# charger.net
KiCad netlist of a schematic drawn in Altium Designer
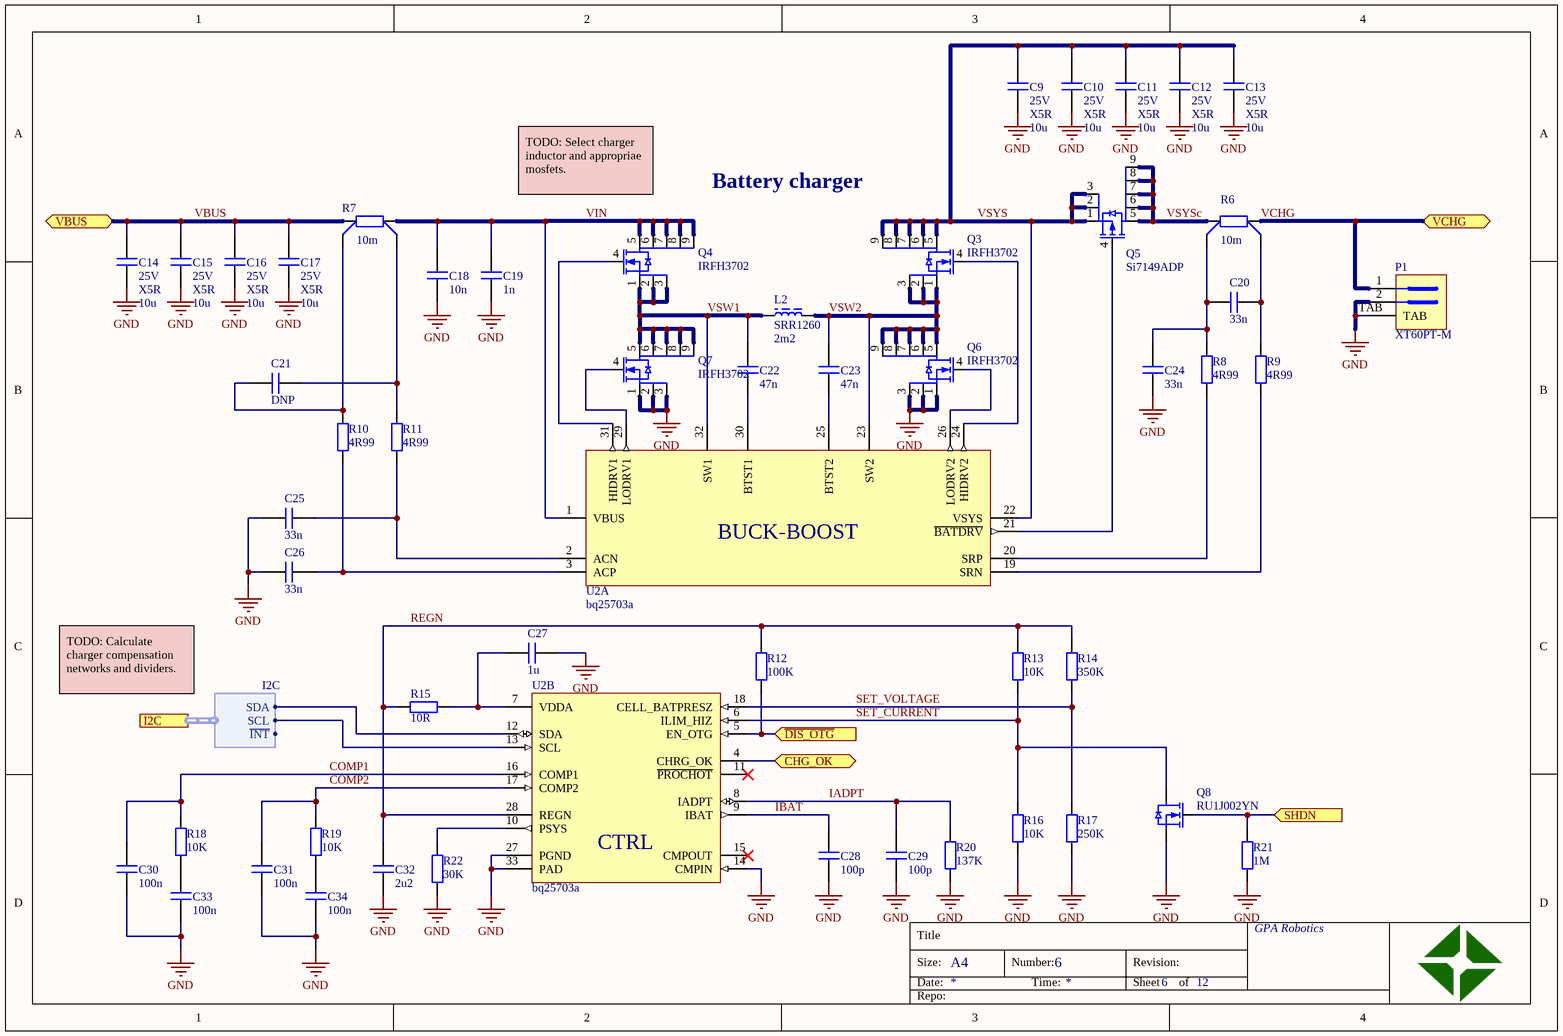
[diagram p0: charger.SchDoc]

(export (version "E")
  (design (tool "Eeschema 10.0.6"))
  (components
    (comp (ref "C9")
      (value "10u")
      (footprint "CAPC3216X14N")
      (description "Capacitor")
      (fields (field (name "VOLTAGE") "25V") (field (name "TYPE") "X5R") (field (name "Comment") "cap"))
      (libsource (lib "lib_passives") (part "cap"))
    )
    (comp (ref "C10")
      (value "10u")
      (footprint "CAPC3216X14N")
      (description "Capacitor")
      (fields (field (name "VOLTAGE") "25V") (field (name "TYPE") "X5R") (field (name "Comment") "cap"))
      (libsource (lib "lib_passives") (part "cap"))
    )
    (comp (ref "C11")
      (value "10u")
      (footprint "CAPC3216X14N")
      (description "Capacitor")
      (fields (field (name "VOLTAGE") "25V") (field (name "TYPE") "X5R") (field (name "Comment") "cap"))
      (libsource (lib "lib_passives") (part "cap"))
    )
    (comp (ref "C12")
      (value "10u")
      (footprint "CAPC3216X14N")
      (description "Capacitor")
      (fields (field (name "VOLTAGE") "25V") (field (name "TYPE") "X5R") (field (name "Comment") "cap"))
      (libsource (lib "lib_passives") (part "cap"))
    )
    (comp (ref "C13")
      (value "10u")
      (footprint "CAPC3216X14N")
      (description "Capacitor")
      (fields (field (name "VOLTAGE") "25V") (field (name "TYPE") "X5R") (field (name "Comment") "cap"))
      (libsource (lib "lib_passives") (part "cap"))
    )
    (comp (ref "C14")
      (value "10u")
      (footprint "CAPC3216X14N")
      (description "Capacitor")
      (fields (field (name "VOLTAGE") "25V") (field (name "TYPE") "X5R") (field (name "Comment") "cap"))
      (libsource (lib "lib_passives") (part "cap"))
    )
    (comp (ref "C15")
      (value "10u")
      (footprint "CAPC3216X14N")
      (description "Capacitor")
      (fields (field (name "VOLTAGE") "25V") (field (name "TYPE") "X5R") (field (name "Comment") "cap"))
      (libsource (lib "lib_passives") (part "cap"))
    )
    (comp (ref "C16")
      (value "10u")
      (footprint "CAPC3216X14N")
      (description "Capacitor")
      (fields (field (name "VOLTAGE") "25V") (field (name "TYPE") "X5R") (field (name "Comment") "cap"))
      (libsource (lib "lib_passives") (part "cap"))
    )
    (comp (ref "C17")
      (value "10u")
      (footprint "CAPC3216X14N")
      (description "Capacitor")
      (fields (field (name "VOLTAGE") "25V") (field (name "TYPE") "X5R") (field (name "Comment") "cap"))
      (libsource (lib "lib_passives") (part "cap"))
    )
    (comp (ref "C18")
      (value "10n")
      (footprint "CAPC1005X06N")
      (description "Capacitor")
      (fields (field (name "Comment") "cap"))
      (libsource (lib "lib_passives") (part "cap"))
    )
    (comp (ref "C19")
      (value "1n")
      (footprint "CAPC1005X06N")
      (description "Capacitor")
      (fields (field (name "Comment") "cap"))
      (libsource (lib "lib_passives") (part "cap"))
    )
    (comp (ref "C20")
      (value "33n")
      (footprint "CAPC1005X06N")
      (description "Capacitor")
      (fields (field (name "Comment") "cap"))
      (libsource (lib "lib_passives") (part "cap"))
    )
    (comp (ref "C21")
      (value "DNP")
      (footprint "CAPC1005X06N")
      (description "Capacitor")
      (fields (field (name "Comment") "cap"))
      (libsource (lib "lib_passives") (part "cap"))
    )
    (comp (ref "C22")
      (value "47n")
      (footprint "CAPC1005X06N")
      (description "Capacitor")
      (fields (field (name "Comment") "cap"))
      (libsource (lib "lib_passives") (part "cap"))
    )
    (comp (ref "C23")
      (value "47n")
      (footprint "CAPC1005X06N")
      (description "Capacitor")
      (fields (field (name "Comment") "cap"))
      (libsource (lib "lib_passives") (part "cap"))
    )
    (comp (ref "C24")
      (value "33n")
      (footprint "CAPC1005X06N")
      (description "Capacitor")
      (fields (field (name "Comment") "cap"))
      (libsource (lib "lib_passives") (part "cap"))
    )
    (comp (ref "C25")
      (value "33n")
      (footprint "CAPC1005X06N")
      (description "Capacitor")
      (fields (field (name "Comment") "cap"))
      (libsource (lib "lib_passives") (part "cap"))
    )
    (comp (ref "C26")
      (value "33n")
      (footprint "CAPC1005X06N")
      (description "Capacitor")
      (fields (field (name "Comment") "cap"))
      (libsource (lib "lib_passives") (part "cap"))
    )
    (comp (ref "C27")
      (value "1u")
      (footprint "CAPC2012X11N")
      (description "Capacitor")
      (fields (field (name "Comment") "cap"))
      (libsource (lib "lib_passives") (part "cap"))
    )
    (comp (ref "C28")
      (value "100p")
      (footprint "CAPC1005X06N")
      (description "Capacitor")
      (fields (field (name "Comment") "cap"))
      (libsource (lib "lib_passives") (part "cap"))
    )
    (comp (ref "C29")
      (value "100p")
      (footprint "CAPC1005X06N")
      (description "Capacitor")
      (fields (field (name "Comment") "cap"))
      (libsource (lib "lib_passives") (part "cap"))
    )
    (comp (ref "C30")
      (value "100n")
      (footprint "CAPC1005X06N")
      (description "Capacitor")
      (fields (field (name "Comment") "cap"))
      (libsource (lib "lib_passives") (part "cap"))
    )
    (comp (ref "C31")
      (value "100n")
      (footprint "CAPC1005X06N")
      (description "Capacitor")
      (fields (field (name "Comment") "cap"))
      (libsource (lib "lib_passives") (part "cap"))
    )
    (comp (ref "C32")
      (value "2u2")
      (footprint "CAPC2012X11N")
      (description "Capacitor")
      (fields (field (name "Comment") "cap"))
      (libsource (lib "lib_passives") (part "cap"))
    )
    (comp (ref "C33")
      (value "100n")
      (footprint "CAPC1005X06N")
      (description "Capacitor")
      (fields (field (name "Comment") "cap"))
      (libsource (lib "lib_passives") (part "cap"))
    )
    (comp (ref "C34")
      (value "100n")
      (footprint "CAPC1005X06N")
      (description "Capacitor")
      (fields (field (name "Comment") "cap"))
      (libsource (lib "lib_passives") (part "cap"))
    )
    (comp (ref "L2")
      (value "SRR1260")
      (footprint "SRR1260")
      (fields (field (name "ALTIUM_VALUE") "2m2"))
      (libsource (lib "lib_bourns") (part "srr1260"))
    )
    (comp (ref "P1")
      (value "XT60PT-M")
      (footprint "XT60PT-M")
      (libsource (lib "lib_amass") (part "xt60pt-m"))
    )
    (comp (ref "Q3")
      (value "IRFH3702")
      (footprint "PQFN67P300X300X100-8N")
      (description "HEXFET Power MOSFET")
      (libsource (lib "lib_infineon") (part "irfh3702"))
    )
    (comp (ref "Q4")
      (value "IRFH3702")
      (footprint "PQFN67P300X300X100-8N")
      (description "HEXFET Power MOSFET")
      (libsource (lib "lib_infineon") (part "irfh3702"))
    )
    (comp (ref "Q5")
      (value "Si7149ADP")
      (footprint "SON127P620X112_HS-9N_POWERPAK_SO8")
      (description "P-Channel 30 V (D-S) MOSFET")
      (libsource (lib "lib_vishay") (part "si7149adp"))
    )
    (comp (ref "Q6")
      (value "IRFH3702")
      (footprint "PQFN67P300X300X100-8N")
      (description "HEXFET Power MOSFET")
      (libsource (lib "lib_infineon") (part "irfh3702"))
    )
    (comp (ref "Q7")
      (value "IRFH3702")
      (footprint "PQFN67P300X300X100-8N")
      (description "HEXFET Power MOSFET")
      (libsource (lib "lib_infineon") (part "irfh3702"))
    )
    (comp (ref "Q8")
      (value "RU1J002YN")
      (footprint "SOTFL65P210X105-3N")
      (description "N-channel 50V 200mA Small signal MOSFET")
      (libsource (lib "lib_rohm") (part "ru1j002yn"))
    )
    (comp (ref "R6")
      (value "10m")
      (footprint "4T_RESC1632X05N")
      (description "Resistor")
      (fields (field (name "Comment") "res_4t"))
      (libsource (lib "") (part "res_4t_1"))
    )
    (comp (ref "R7")
      (value "10m")
      (footprint "4T_RESC1632X05N")
      (description "Resistor")
      (fields (field (name "Comment") "res_4t"))
      (libsource (lib "lib_passives") (part "res_4t"))
    )
    (comp (ref "R8")
      (value "4R99")
      (footprint "RESC1005X04N")
      (description "Resistor")
      (fields (field (name "Comment") "res"))
      (libsource (lib "lib_passives") (part "res"))
    )
    (comp (ref "R9")
      (value "4R99")
      (footprint "RESC1005X04N")
      (description "Resistor")
      (fields (field (name "Comment") "res"))
      (libsource (lib "lib_passives") (part "res"))
    )
    (comp (ref "R10")
      (value "4R99")
      (footprint "RESC1005X04N")
      (description "Resistor")
      (fields (field (name "Comment") "res"))
      (libsource (lib "lib_passives") (part "res"))
    )
    (comp (ref "R11")
      (value "4R99")
      (footprint "RESC1005X04N")
      (description "Resistor")
      (fields (field (name "Comment") "res"))
      (libsource (lib "lib_passives") (part "res"))
    )
    (comp (ref "R12")
      (value "100K")
      (footprint "RESC1005X04N")
      (description "Resistor")
      (fields (field (name "Comment") "res"))
      (libsource (lib "lib_passives") (part "res"))
    )
    (comp (ref "R13")
      (value "10K")
      (footprint "RESC1005X04N")
      (description "Resistor")
      (fields (field (name "Comment") "res"))
      (libsource (lib "lib_passives") (part "res"))
    )
    (comp (ref "R14")
      (value "350K")
      (footprint "RESC1005X04N")
      (description "Resistor")
      (fields (field (name "Comment") "res"))
      (libsource (lib "lib_passives") (part "res"))
    )
    (comp (ref "R15")
      (value "10R")
      (footprint "RESC1005X04N")
      (description "Resistor")
      (fields (field (name "Comment") "res"))
      (libsource (lib "") (part "res_1"))
    )
    (comp (ref "R16")
      (value "10K")
      (footprint "RESC1005X04N")
      (description "Resistor")
      (fields (field (name "Comment") "res"))
      (libsource (lib "lib_passives") (part "res"))
    )
    (comp (ref "R17")
      (value "250K")
      (footprint "RESC1005X04N")
      (description "Resistor")
      (fields (field (name "Comment") "res"))
      (libsource (lib "lib_passives") (part "res"))
    )
    (comp (ref "R18")
      (value "10K")
      (footprint "RESC1005X04N")
      (description "Resistor")
      (fields (field (name "Comment") "res"))
      (libsource (lib "lib_passives") (part "res"))
    )
    (comp (ref "R19")
      (value "10K")
      (footprint "RESC1005X04N")
      (description "Resistor")
      (fields (field (name "Comment") "res"))
      (libsource (lib "lib_passives") (part "res"))
    )
    (comp (ref "R20")
      (value "137K")
      (footprint "RESC1005X04N")
      (description "Resistor")
      (fields (field (name "Comment") "res"))
      (libsource (lib "lib_passives") (part "res"))
    )
    (comp (ref "R21")
      (value "1M")
      (footprint "RESC1005X04N")
      (description "Resistor")
      (fields (field (name "Comment") "res"))
      (libsource (lib "lib_passives") (part "res"))
    )
    (comp (ref "R22")
      (value "30K")
      (footprint "RESC1005X04N")
      (description "Resistor")
      (fields (field (name "Comment") "res"))
      (libsource (lib "lib_passives") (part "res"))
    )
    (comp (ref "U2")
      (value "bq25703a")
      (footprint "QFN40P400X400X80_HS-33N_BQ25703A")
      (libsource (lib "lib_ti") (part "bq25703a"))
    )
  )
  (nets
    (net (code "2") (name "/CHG_OK") (class "Default")
      (node (ref "U2") (pin "4") (pinfunction "CHRG_OK_4") (pintype "open_collector"))
    )
    (net (code "3") (name "/COMP1") (class "Default")
      (node (ref "C30") (pin "2") (pinfunction "2_2") (pintype "passive"))
      (node (ref "R18") (pin "2") (pinfunction "2_2") (pintype "passive"))
      (node (ref "U2") (pin "16") (pinfunction "COMP1_16") (pintype "input"))
    )
    (net (code "4") (name "/COMP2") (class "Default")
      (node (ref "C31") (pin "2") (pinfunction "2_2") (pintype "passive"))
      (node (ref "R19") (pin "2") (pinfunction "2_2") (pintype "passive"))
      (node (ref "U2") (pin "17") (pinfunction "COMP2_17") (pintype "input"))
    )
    (net (code "5") (name "/DIS_OTG") (class "Default")
      (node (ref "R12") (pin "1") (pinfunction "1_1") (pintype "passive"))
      (node (ref "U2") (pin "5") (pinfunction "EN_OTG_5") (pintype "input"))
    )
    (net (code "6") (name "/IADPT") (class "Default")
      (node (ref "C29") (pin "2") (pinfunction "2_2") (pintype "passive"))
      (node (ref "R20") (pin "2") (pinfunction "2_2") (pintype "passive"))
      (node (ref "U2") (pin "8") (pinfunction "IADPT_8") (pintype "bidirectional"))
    )
    (net (code "7") (name "/IBAT") (class "Default")
      (node (ref "C28") (pin "2") (pinfunction "2_2") (pintype "passive"))
      (node (ref "U2") (pin "9") (pinfunction "IBAT_9") (pintype "output"))
    )
    (net (code "8") (name "/REGN") (class "Default")
      (node (ref "C32") (pin "2") (pinfunction "2_2") (pintype "passive"))
      (node (ref "R12") (pin "2") (pinfunction "2_2") (pintype "passive"))
      (node (ref "R13") (pin "2") (pinfunction "2_2") (pintype "passive"))
      (node (ref "R14") (pin "2") (pinfunction "2_2") (pintype "passive"))
      (node (ref "R15") (pin "1") (pinfunction "1_1") (pintype "passive"))
      (node (ref "U2") (pin "28") (pinfunction "REGN_28") (pintype "power_in"))
    )
    (net (code "9") (name "/SCL") (class "Default")
      (node (ref "U2") (pin "13") (pinfunction "SCL_13") (pintype "input"))
    )
    (net (code "10") (name "/SDA") (class "Default")
      (node (ref "U2") (pin "12") (pinfunction "SDA_12") (pintype "bidirectional"))
    )
    (net (code "11") (name "/SET_CURRENT") (class "Default")
      (node (ref "Q8") (pin "3") (pinfunction "D_3") (pintype "passive"))
      (node (ref "R13") (pin "1") (pinfunction "1_1") (pintype "passive"))
      (node (ref "R16") (pin "2") (pinfunction "2_2") (pintype "passive"))
      (node (ref "U2") (pin "6") (pinfunction "ILIM_HIZ_6") (pintype "input"))
    )
    (net (code "12") (name "/SET_VOLTAGE") (class "Default")
      (node (ref "R14") (pin "1") (pinfunction "1_1") (pintype "passive"))
      (node (ref "R17") (pin "2") (pinfunction "2_2") (pintype "passive"))
      (node (ref "U2") (pin "18") (pinfunction "CELL_BATPRESZ_18") (pintype "input"))
    )
    (net (code "13") (name "/SHDN") (class "Default")
      (node (ref "Q8") (pin "1") (pinfunction "G_1") (pintype "passive"))
      (node (ref "R21") (pin "2") (pinfunction "2_2") (pintype "passive"))
    )
    (net (code "14") (name "/VBUS") (class "Default")
      (node (ref "C14") (pin "2") (pinfunction "2_2") (pintype "passive"))
      (node (ref "C15") (pin "2") (pinfunction "2_2") (pintype "passive"))
      (node (ref "C16") (pin "2") (pinfunction "2_2") (pintype "passive"))
      (node (ref "C17") (pin "2") (pinfunction "2_2") (pintype "passive"))
      (node (ref "R7") (pin "1") (pinfunction "1_1") (pintype "passive"))
    )
    (net (code "15") (name "/VCHG") (class "Default")
      (node (ref "P1") (pin "1") (pinfunction "1_1") (pintype "passive"))
      (node (ref "R6") (pin "1") (pinfunction "1_1") (pintype "passive"))
    )
    (net (code "16") (name "/VIN") (class "Default")
      (node (ref "C18") (pin "2") (pinfunction "2_2") (pintype "passive"))
      (node (ref "C19") (pin "2") (pinfunction "2_2") (pintype "passive"))
      (node (ref "Q4") (pin "5") (pinfunction "D_5") (pintype "passive"))
      (node (ref "Q4") (pin "6") (pinfunction "D_6") (pintype "passive"))
      (node (ref "Q4") (pin "7") (pinfunction "D_7") (pintype "passive"))
      (node (ref "Q4") (pin "8") (pinfunction "D_8") (pintype "passive"))
      (node (ref "Q4") (pin "9") (pinfunction "D_9") (pintype "passive"))
      (node (ref "R7") (pin "2") (pinfunction "2_2") (pintype "passive"))
      (node (ref "U2") (pin "1") (pinfunction "VBUS_1") (pintype "power_in"))
    )
    (net (code "17") (name "/VSW1") (class "Default")
      (node (ref "C22") (pin "2") (pinfunction "2_2") (pintype "passive"))
      (node (ref "L2") (pin "1") (pinfunction "1_1") (pintype "passive"))
      (node (ref "Q4") (pin "1") (pinfunction "S_1") (pintype "passive"))
      (node (ref "Q4") (pin "2") (pinfunction "S_2") (pintype "passive"))
      (node (ref "Q4") (pin "3") (pinfunction "S_3") (pintype "passive"))
      (node (ref "Q7") (pin "5") (pinfunction "D_5") (pintype "passive"))
      (node (ref "Q7") (pin "6") (pinfunction "D_6") (pintype "passive"))
      (node (ref "Q7") (pin "7") (pinfunction "D_7") (pintype "passive"))
      (node (ref "Q7") (pin "8") (pinfunction "D_8") (pintype "passive"))
      (node (ref "Q7") (pin "9") (pinfunction "D_9") (pintype "passive"))
      (node (ref "U2") (pin "32") (pinfunction "SW1_32") (pintype "power_in"))
    )
    (net (code "18") (name "/VSW2") (class "Default")
      (node (ref "C23") (pin "2") (pinfunction "2_2") (pintype "passive"))
      (node (ref "L2") (pin "2") (pinfunction "2_2") (pintype "passive"))
      (node (ref "Q3") (pin "1") (pinfunction "S_1") (pintype "passive"))
      (node (ref "Q3") (pin "2") (pinfunction "S_2") (pintype "passive"))
      (node (ref "Q3") (pin "3") (pinfunction "S_3") (pintype "passive"))
      (node (ref "Q6") (pin "5") (pinfunction "D_5") (pintype "passive"))
      (node (ref "Q6") (pin "6") (pinfunction "D_6") (pintype "passive"))
      (node (ref "Q6") (pin "7") (pinfunction "D_7") (pintype "passive"))
      (node (ref "Q6") (pin "8") (pinfunction "D_8") (pintype "passive"))
      (node (ref "Q6") (pin "9") (pinfunction "D_9") (pintype "passive"))
      (node (ref "U2") (pin "23") (pinfunction "SW2_23") (pintype "power_in"))
    )
    (net (code "19") (name "/VSYS") (class "Default")
      (node (ref "C10") (pin "2") (pinfunction "2_2") (pintype "passive"))
      (node (ref "C11") (pin "2") (pinfunction "2_2") (pintype "passive"))
      (node (ref "C12") (pin "2") (pinfunction "2_2") (pintype "passive"))
      (node (ref "C13") (pin "2") (pinfunction "2_2") (pintype "passive"))
      (node (ref "C9") (pin "2") (pinfunction "2_2") (pintype "passive"))
      (node (ref "Q3") (pin "5") (pinfunction "D_5") (pintype "passive"))
      (node (ref "Q3") (pin "6") (pinfunction "D_6") (pintype "passive"))
      (node (ref "Q3") (pin "7") (pinfunction "D_7") (pintype "passive"))
      (node (ref "Q3") (pin "8") (pinfunction "D_8") (pintype "passive"))
      (node (ref "Q3") (pin "9") (pinfunction "D_9") (pintype "passive"))
      (node (ref "Q5") (pin "1") (pinfunction "S_1") (pintype "passive"))
      (node (ref "Q5") (pin "2") (pinfunction "S_2") (pintype "passive"))
      (node (ref "Q5") (pin "3") (pinfunction "S_3") (pintype "passive"))
      (node (ref "U2") (pin "22") (pinfunction "VSYS_22") (pintype "power_in"))
    )
    (net (code "20") (name "/VSYSc") (class "Default")
      (node (ref "Q5") (pin "5") (pinfunction "D_5") (pintype "passive"))
      (node (ref "Q5") (pin "6") (pinfunction "D_6") (pintype "passive"))
      (node (ref "Q5") (pin "7") (pinfunction "D_7") (pintype "passive"))
      (node (ref "Q5") (pin "8") (pinfunction "D_8") (pintype "passive"))
      (node (ref "Q5") (pin "9") (pinfunction "D_9") (pintype "passive"))
      (node (ref "R6") (pin "2") (pinfunction "2_2") (pintype "passive"))
    )
    (net (code "22") (name "GND") (class "Default")
      (node (ref "C10") (pin "1") (pinfunction "1_1") (pintype "passive"))
      (node (ref "C11") (pin "1") (pinfunction "1_1") (pintype "passive"))
      (node (ref "C12") (pin "1") (pinfunction "1_1") (pintype "passive"))
      (node (ref "C13") (pin "1") (pinfunction "1_1") (pintype "passive"))
      (node (ref "C14") (pin "1") (pinfunction "1_1") (pintype "passive"))
      (node (ref "C15") (pin "1") (pinfunction "1_1") (pintype "passive"))
      (node (ref "C16") (pin "1") (pinfunction "1_1") (pintype "passive"))
      (node (ref "C17") (pin "1") (pinfunction "1_1") (pintype "passive"))
      (node (ref "C18") (pin "1") (pinfunction "1_1") (pintype "passive"))
      (node (ref "C19") (pin "1") (pinfunction "1_1") (pintype "passive"))
      (node (ref "C24") (pin "1") (pinfunction "1_1") (pintype "passive"))
      (node (ref "C25") (pin "2") (pinfunction "2_2") (pintype "passive"))
      (node (ref "C26") (pin "2") (pinfunction "2_2") (pintype "passive"))
      (node (ref "C27") (pin "2") (pinfunction "2_2") (pintype "passive"))
      (node (ref "C28") (pin "1") (pinfunction "1_1") (pintype "passive"))
      (node (ref "C29") (pin "1") (pinfunction "1_1") (pintype "passive"))
      (node (ref "C30") (pin "1") (pinfunction "1_1") (pintype "passive"))
      (node (ref "C31") (pin "1") (pinfunction "1_1") (pintype "passive"))
      (node (ref "C32") (pin "1") (pinfunction "1_1") (pintype "passive"))
      (node (ref "C33") (pin "1") (pinfunction "1_1") (pintype "passive"))
      (node (ref "C34") (pin "1") (pinfunction "1_1") (pintype "passive"))
      (node (ref "C9") (pin "1") (pinfunction "1_1") (pintype "passive"))
      (node (ref "P1") (pin "2") (pinfunction "2_2") (pintype "passive"))
      (node (ref "P1") (pin "TAB") (pinfunction "TAB_TAB") (pintype "passive"))
      (node (ref "Q6") (pin "1") (pinfunction "S_1") (pintype "passive"))
      (node (ref "Q6") (pin "2") (pinfunction "S_2") (pintype "passive"))
      (node (ref "Q6") (pin "3") (pinfunction "S_3") (pintype "passive"))
      (node (ref "Q7") (pin "1") (pinfunction "S_1") (pintype "passive"))
      (node (ref "Q7") (pin "2") (pinfunction "S_2") (pintype "passive"))
      (node (ref "Q7") (pin "3") (pinfunction "S_3") (pintype "passive"))
      (node (ref "Q8") (pin "2") (pinfunction "S_2") (pintype "passive"))
      (node (ref "R16") (pin "1") (pinfunction "1_1") (pintype "passive"))
      (node (ref "R17") (pin "1") (pinfunction "1_1") (pintype "passive"))
      (node (ref "R20") (pin "1") (pinfunction "1_1") (pintype "passive"))
      (node (ref "R21") (pin "1") (pinfunction "1_1") (pintype "passive"))
      (node (ref "R22") (pin "1") (pinfunction "1_1") (pintype "passive"))
      (node (ref "U2") (pin "14") (pinfunction "CMPIN_14") (pintype "input"))
      (node (ref "U2") (pin "27") (pinfunction "PGND_27") (pintype "power_in"))
      (node (ref "U2") (pin "33") (pinfunction "PAD_33") (pintype "power_in"))
    )
    (net (code "23") (name "Net-(C20-Pad1)") (class "Default")
      (node (ref "C20") (pin "1") (pinfunction "1_1") (pintype "passive"))
      (node (ref "R6") (pin "3") (pinfunction "3_3") (pintype "passive"))
      (node (ref "R9") (pin "2") (pinfunction "2_2") (pintype "passive"))
    )
    (net (code "24") (name "Net-(C20-Pad2)") (class "Default")
      (node (ref "C20") (pin "2") (pinfunction "2_2") (pintype "passive"))
      (node (ref "C24") (pin "2") (pinfunction "2_2") (pintype "passive"))
      (node (ref "R6") (pin "4") (pinfunction "4_4") (pintype "passive"))
      (node (ref "R8") (pin "2") (pinfunction "2_2") (pintype "passive"))
    )
    (net (code "25") (name "Net-(C21-Pad1)") (class "Default")
      (node (ref "C21") (pin "1") (pinfunction "1_1") (pintype "passive"))
      (node (ref "R11") (pin "2") (pinfunction "2_2") (pintype "passive"))
      (node (ref "R7") (pin "4") (pinfunction "4_4") (pintype "passive"))
    )
    (net (code "26") (name "Net-(C21-Pad2)") (class "Default")
      (node (ref "C21") (pin "2") (pinfunction "2_2") (pintype "passive"))
      (node (ref "R10") (pin "2") (pinfunction "2_2") (pintype "passive"))
      (node (ref "R7") (pin "3") (pinfunction "3_3") (pintype "passive"))
    )
    (net (code "27") (name "Net-(C33-Pad2)") (class "Default")
      (node (ref "C33") (pin "2") (pinfunction "2_2") (pintype "passive"))
      (node (ref "R18") (pin "1") (pinfunction "1_1") (pintype "passive"))
    )
    (net (code "28") (name "Net-(C34-Pad2)") (class "Default")
      (node (ref "C34") (pin "2") (pinfunction "2_2") (pintype "passive"))
      (node (ref "R19") (pin "1") (pinfunction "1_1") (pintype "passive"))
    )
    (net (code "29") (name "Net-(Q3-G)") (class "Default")
      (node (ref "Q3") (pin "4") (pinfunction "G_4") (pintype "passive"))
      (node (ref "U2") (pin "24") (pinfunction "HIDRV2_24") (pintype "output"))
    )
    (net (code "30") (name "Net-(Q4-G)") (class "Default")
      (node (ref "Q4") (pin "4") (pinfunction "G_4") (pintype "passive"))
      (node (ref "U2") (pin "31") (pinfunction "HIDRV1_31") (pintype "output"))
    )
    (net (code "31") (name "Net-(Q5-G)") (class "Default")
      (node (ref "Q5") (pin "4") (pinfunction "G_4") (pintype "passive"))
      (node (ref "U2") (pin "21") (pinfunction "BATDRV_21") (pintype "output"))
    )
    (net (code "32") (name "Net-(Q6-G)") (class "Default")
      (node (ref "Q6") (pin "4") (pinfunction "G_4") (pintype "passive"))
      (node (ref "U2") (pin "26") (pinfunction "LODRV2_26") (pintype "output"))
    )
    (net (code "33") (name "Net-(Q7-G)") (class "Default")
      (node (ref "Q7") (pin "4") (pinfunction "G_4") (pintype "passive"))
      (node (ref "U2") (pin "29") (pinfunction "LODRV1_29") (pintype "output"))
    )
    (net (code "34") (name "Net-(U2A-ACN)") (class "Default")
      (node (ref "C25") (pin "1") (pinfunction "1_1") (pintype "passive"))
      (node (ref "R11") (pin "1") (pinfunction "1_1") (pintype "passive"))
      (node (ref "U2") (pin "2") (pinfunction "ACN_2") (pintype "power_in"))
    )
    (net (code "35") (name "Net-(U2A-ACP)") (class "Default")
      (node (ref "C26") (pin "1") (pinfunction "1_1") (pintype "passive"))
      (node (ref "R10") (pin "1") (pinfunction "1_1") (pintype "passive"))
      (node (ref "U2") (pin "3") (pinfunction "ACP_3") (pintype "power_in"))
    )
    (net (code "36") (name "Net-(U2A-BTST1)") (class "Default")
      (node (ref "C22") (pin "1") (pinfunction "1_1") (pintype "passive"))
      (node (ref "U2") (pin "30") (pinfunction "BTST1_30") (pintype "power_in"))
    )
    (net (code "37") (name "Net-(U2A-BTST2)") (class "Default")
      (node (ref "C23") (pin "1") (pinfunction "1_1") (pintype "passive"))
      (node (ref "U2") (pin "25") (pinfunction "BTST2_25") (pintype "power_in"))
    )
    (net (code "38") (name "Net-(U2A-SRN)") (class "Default")
      (node (ref "R9") (pin "1") (pinfunction "1_1") (pintype "passive"))
      (node (ref "U2") (pin "19") (pinfunction "SRN_19") (pintype "power_in"))
    )
    (net (code "39") (name "Net-(U2A-SRP)") (class "Default")
      (node (ref "R8") (pin "1") (pinfunction "1_1") (pintype "passive"))
      (node (ref "U2") (pin "20") (pinfunction "SRP_20") (pintype "power_in"))
    )
    (net (code "40") (name "Net-(U2B-PSYS)") (class "Default")
      (node (ref "R22") (pin "2") (pinfunction "2_2") (pintype "passive"))
      (node (ref "U2") (pin "10") (pinfunction "PSYS_10") (pintype "output"))
    )
    (net (code "41") (name "Net-(U2B-VDDA)") (class "Default")
      (node (ref "C27") (pin "1") (pinfunction "1_1") (pintype "passive"))
      (node (ref "R15") (pin "2") (pinfunction "2_2") (pintype "passive"))
      (node (ref "U2") (pin "7") (pinfunction "VDDA_7") (pintype "power_in"))
    )
    (net (code "42") (name "unconnected-(U2B-CMPOUT-Pad15)") (class "Default")
      (node (ref "U2") (pin "15") (pinfunction "CMPOUT_15") (pintype "open_collector+no_connect"))
    )
    (net (code "43") (name "unconnected-(U2B-PROCHOT-Pad11)") (class "Default")
      (node (ref "U2") (pin "11") (pinfunction "PROCHOT_11") (pintype "open_collector+no_connect"))
    )
  )
)
